# whistlev2.net
KiCad netlist of a schematic drawn in EAGLE
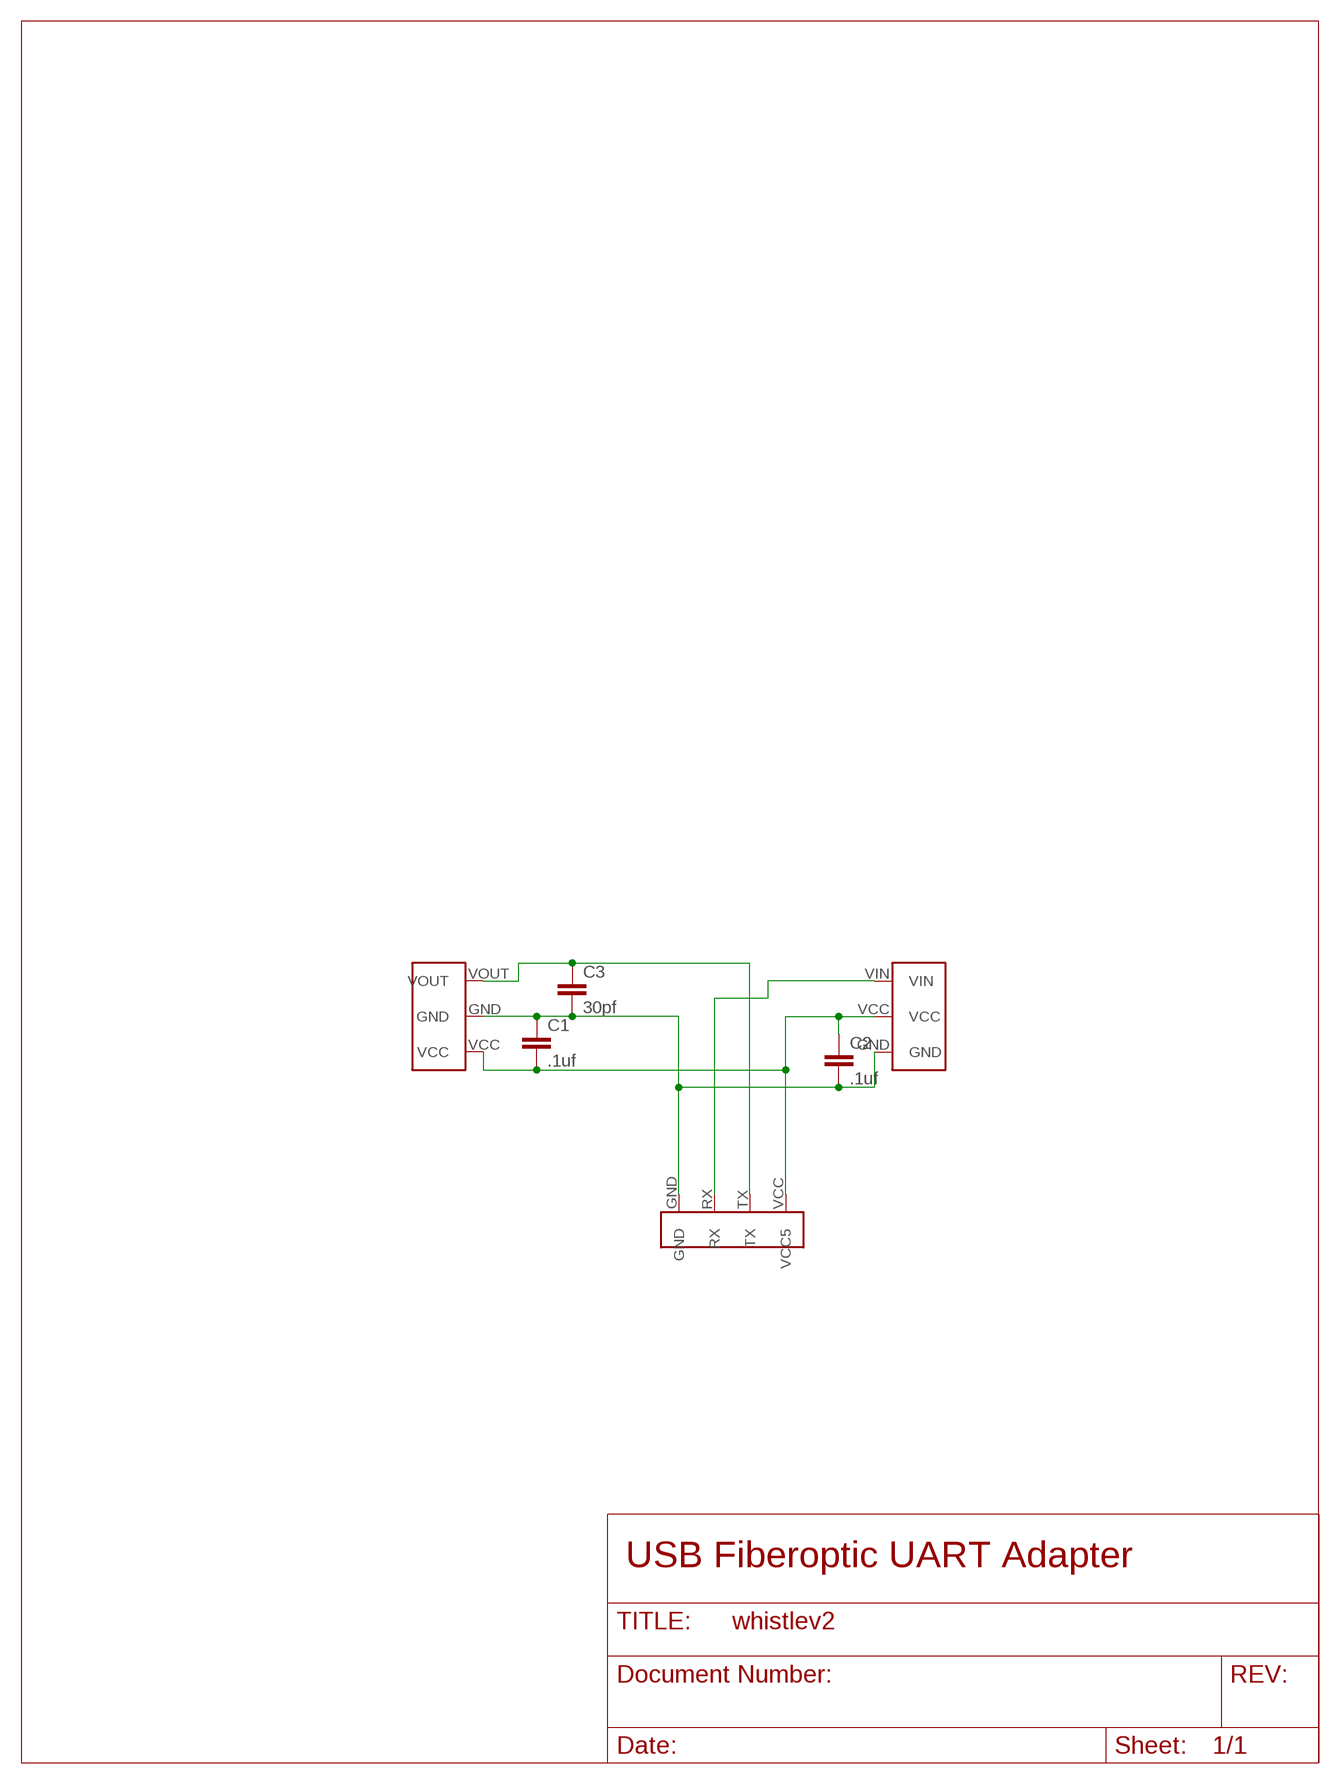
[diagram p0: schematic, sheet 1]

(export (version "E")
  (design (tool "Eeschema 10.0.6"))
  (components
    (comp (ref "C1")
      (value ".1uf")
      (footprint "eagle-import:0805")
      (libsource (lib "eagle-import") (part "CAP0805"))
    )
    (comp (ref "C2")
      (value ".1uf")
      (footprint "eagle-import:0805")
      (libsource (lib "eagle-import") (part "CAP0805"))
    )
    (comp (ref "C3")
      (value "30pf")
      (footprint "eagle-import:0805")
      (libsource (lib "eagle-import") (part "CAP0805"))
    )
    (comp (ref "U$1")
      (value "DLR1160")
      (footprint "eagle-import:DLR")
      (libsource (lib "eagle-import") (part "DLR1160"))
    )
    (comp (ref "U$2")
      (value "DLT1160")
      (footprint "eagle-import:DLT")
      (libsource (lib "eagle-import") (part "DLT1160"))
    )
    (comp (ref "U$3")
      (value "RS")
      (footprint "eagle-import:RS-232")
      (libsource (lib "eagle-import") (part "RS"))
    )
  )
  (nets
    (net (code "1") (name "Net-(C1-Pad1)") (class "Default")
      (node (ref "C1") (pin "1") (pinfunction "1_1") (pintype "passive"))
      (node (ref "C2") (pin "2") (pinfunction "2_2") (pintype "passive"))
      (node (ref "C3") (pin "2") (pinfunction "2_2") (pintype "passive"))
      (node (ref "U$1") (pin "GND") (pinfunction "GND_GND") (pintype "bidirectional"))
      (node (ref "U$2") (pin "GND") (pinfunction "GND_GND") (pintype "bidirectional"))
      (node (ref "U$3") (pin "GND") (pinfunction "GND_GND") (pintype "bidirectional"))
    )
    (net (code "2") (name "Net-(C3-Pad1)") (class "Default")
      (node (ref "C3") (pin "1") (pinfunction "1_1") (pintype "passive"))
      (node (ref "U$1") (pin "VOUT") (pinfunction "VOUT_VOUT") (pintype "bidirectional"))
      (node (ref "U$3") (pin "TX") (pinfunction "TX_TX") (pintype "bidirectional"))
    )
    (net (code "3") (name "Net-(U$2-PadVIN)") (class "Default")
      (node (ref "U$2") (pin "VIN") (pinfunction "VIN_VIN") (pintype "bidirectional"))
      (node (ref "U$3") (pin "RX") (pinfunction "RX_RX") (pintype "bidirectional"))
    )
    (net (code "4") (name "Net-(U$3-VCC5)") (class "Default")
      (node (ref "C1") (pin "2") (pinfunction "2_2") (pintype "passive"))
      (node (ref "C2") (pin "1") (pinfunction "1_1") (pintype "passive"))
      (node (ref "U$1") (pin "VCC") (pinfunction "VCC_VCC") (pintype "bidirectional"))
      (node (ref "U$2") (pin "VCC") (pinfunction "VCC_VCC") (pintype "bidirectional"))
      (node (ref "U$3") (pin "VCC") (pinfunction "VCC5_VCC") (pintype "bidirectional"))
    )
  )
)
